# BEEP.net
KiCad netlist of a schematic drawn in Altium Designer
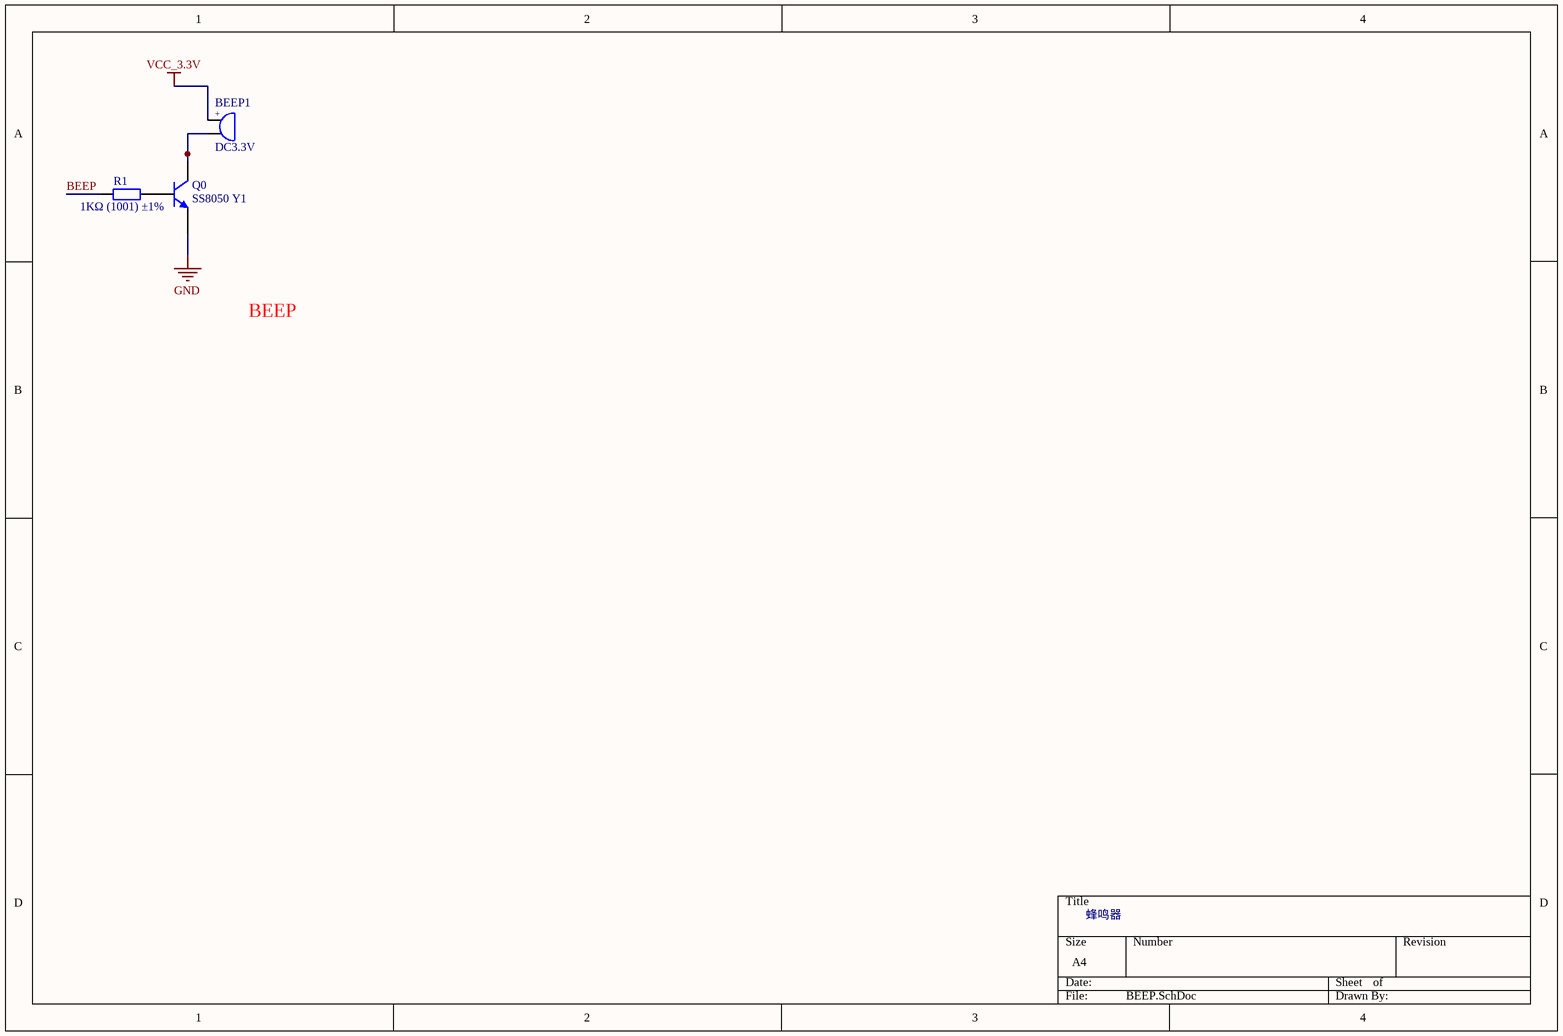
[diagram p0: BEEP.SchDoc]

(export (version "E")
  (design (tool "Eeschema 10.0.6"))
  (components
    (comp (ref "BEEP1")
      (value "DC3.3V")
      (footprint "BUZZ_7.6")
      (description "蜂鸣器")
      (libsource (lib "未分类器件") (part "BEEP"))
    )
    (comp (ref "Q0")
      (value "SS8050 Y1")
      (footprint "SOT-23(SOT-23-3)")
      (description "三极管")
      (libsource (lib "Miscellaneous Devices LC") (part "SOT-23 SS8050 Y1"))
    )
    (comp (ref "R1")
      (value "1KΩ (1001) ±1%")
      (footprint "RESC_0603_2")
      (description "贴片电阻")
      (libsource (lib "RES") (part "0603 1KΩ (1001) 1%"))
    )
  )
  (nets
    (net (code "1") (name "/BEEP") (class "Default")
      (node (ref "R1") (pin "1") (pinfunction "1_1") (pintype "passive"))
    )
    (net (code "2") (name "GND") (class "Default")
      (node (ref "Q0") (pin "2") (pinfunction "E_2") (pintype "passive"))
    )
    (net (code "3") (name "Net-(Q0-C)") (class "Default")
      (node (ref "BEEP1") (pin "2") (pinfunction "2_2") (pintype "passive"))
      (node (ref "Q0") (pin "3") (pinfunction "C_3") (pintype "passive"))
    )
    (net (code "4") (name "VCC_3.3V") (class "Default")
      (node (ref "BEEP1") (pin "1") (pinfunction "1_1") (pintype "passive"))
    )
    (net (code "5") (name "unconnected-(Q0-B-Pad1)") (class "Default")
      (node (ref "Q0") (pin "1") (pinfunction "B_1") (pintype "passive"))
    )
    (net (code "6") (name "unconnected-(R1-Pad2)") (class "Default")
      (node (ref "R1") (pin "2") (pinfunction "2_2") (pintype "passive"))
    )
  )
)
